# ATMegaBoardReduced.net
KiCad netlist of a schematic drawn in EAGLE
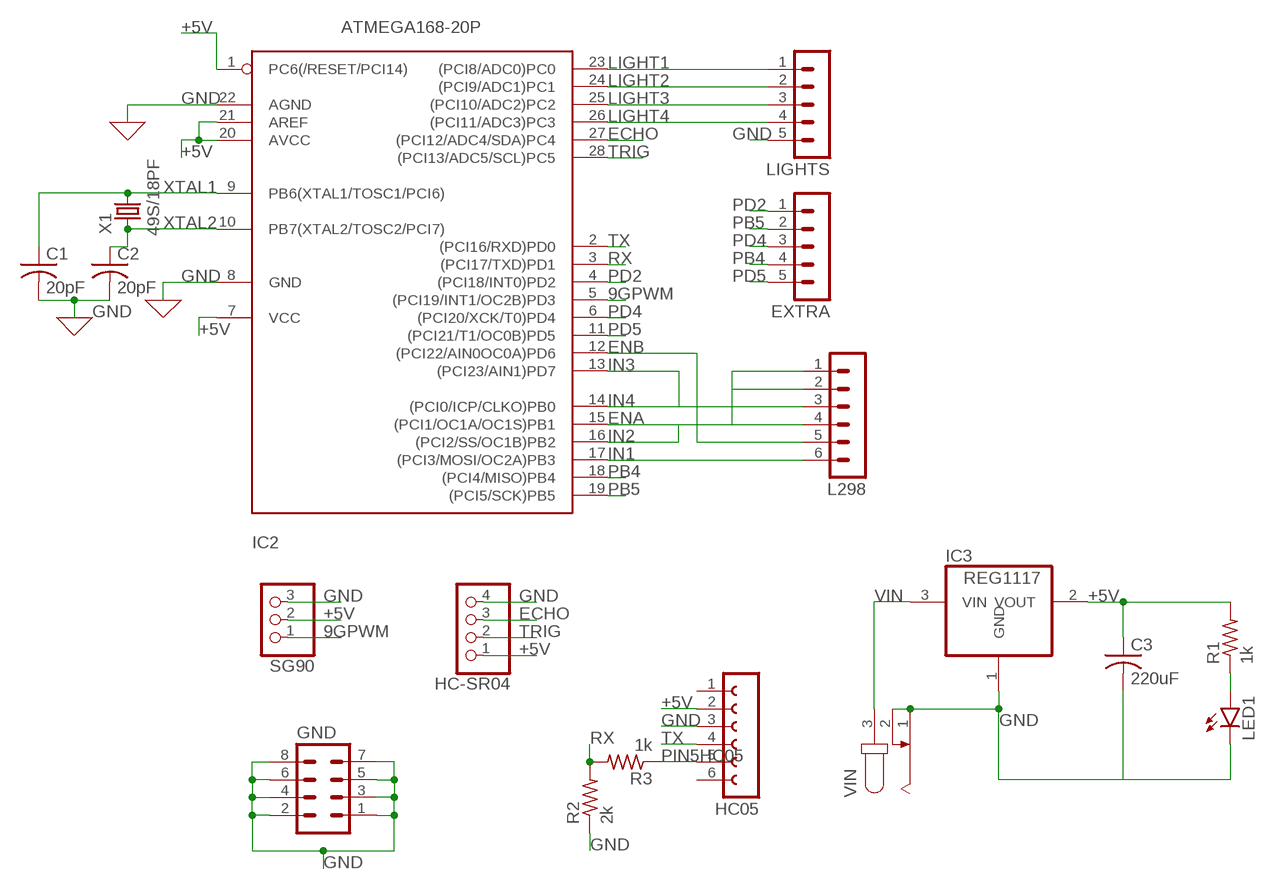
[diagram p0: schematic, sheet 1]

(export (version "E")
  (design (tool "Eeschema 10.0.6"))
  (components
    (comp (ref "C1")
      (value "20pF")
      (footprint "eagle-import:C050-024X044")
      (libsource (lib "eagle-import") (part "C-US050-024X044"))
    )
    (comp (ref "C2")
      (value "20pF")
      (footprint "eagle-import:C050-024X044")
      (libsource (lib "eagle-import") (part "C-US050-024X044"))
    )
    (comp (ref "C3")
      (value "220uF")
      (footprint "eagle-import:C050-024X044")
      (libsource (lib "eagle-import") (part "C-US050-024X044"))
    )
    (comp (ref "EXTRA")
      (value "MA05-1")
      (footprint "eagle-import:MA05-1")
      (libsource (lib "eagle-import") (part "MA05-1"))
    )
    (comp (ref "GND")
      (value "MA04-2")
      (footprint "eagle-import:MA04-2")
      (libsource (lib "eagle-import") (part "MA04-2"))
    )
    (comp (ref "HC-SR04")
      (value "PINHD-1X4")
      (footprint "eagle-import:1X04")
      (libsource (lib "eagle-import") (part "PINHD-1X4"))
    )
    (comp (ref "HC05")
      (value "FE06W")
      (footprint "eagle-import:FE06W")
      (libsource (lib "eagle-import") (part "FE06W"))
    )
    (comp (ref "IC2")
      (value "ATMEGA168-20P")
      (footprint "eagle-import:DIL28-3")
      (libsource (lib "eagle-import") (part "ATMEGA168P-20"))
    )
    (comp (ref "IC3")
      (value "REG1117")
      (footprint "eagle-import:SOT223")
      (libsource (lib "eagle-import") (part "REG1117"))
    )
    (comp (ref "L298")
      (value "MA06-1")
      (footprint "eagle-import:MA06-1")
      (libsource (lib "eagle-import") (part "MA06-1"))
    )
    (comp (ref "LED1")
      (value "LED5MM")
      (footprint "eagle-import:LED5MM")
      (libsource (lib "eagle-import") (part "LED5MM"))
    )
    (comp (ref "LIGHTS")
      (value "MA05-1")
      (footprint "eagle-import:MA05-1")
      (libsource (lib "eagle-import") (part "MA05-1"))
    )
    (comp (ref "R1")
      (value "1k")
      (footprint "eagle-import:0207_10")
      (libsource (lib "eagle-import") (part "R-US_0207/10"))
    )
    (comp (ref "R2")
      (value "2k")
      (footprint "eagle-import:0207_10")
      (libsource (lib "eagle-import") (part "R-US_0207/10"))
    )
    (comp (ref "R3")
      (value "1k")
      (footprint "eagle-import:0207_10")
      (libsource (lib "eagle-import") (part "R-US_0207/10"))
    )
    (comp (ref "SG90")
      (value "PINHD-1X3")
      (footprint "eagle-import:1X03")
      (libsource (lib "eagle-import") (part "PINHD-1X3"))
    )
    (comp (ref "VIN")
      (value "JACK-PLUG1")
      (footprint "eagle-import:SPC4078")
      (libsource (lib "eagle-import") (part "JACK-PLUG1"))
    )
    (comp (ref "X1")
      (value "49S/18PF")
      (footprint "eagle-import:XTAL_HC49")
      (fields (field (name "MANUFACTURER") "Xinhunjing ") (field (name "CREATED_BY") "PCBLayout.com"))
      (libsource (lib "eagle-import") (part "49S/18PF"))
    )
  )
  (nets
    (net (code "1") (name "/+5V") (class "Default")
      (node (ref "C3") (pin "1") (pinfunction "1_1") (pintype "passive"))
      (node (ref "HC-SR04") (pin "1") (pinfunction "1_1") (pintype "passive"))
      (node (ref "HC05") (pin "2") (pinfunction "2_2") (pintype "passive"))
      (node (ref "IC2") (pin "1") (pinfunction "PC6(/RESET/PCI14)_1") (pintype "bidirectional"))
      (node (ref "IC2") (pin "20") (pinfunction "AVCC_20") (pintype "bidirectional"))
      (node (ref "IC2") (pin "21") (pinfunction "AREF_21") (pintype "bidirectional"))
      (node (ref "IC2") (pin "7") (pinfunction "VCC_7") (pintype "bidirectional"))
      (node (ref "IC3") (pin "2") (pinfunction "VOUT_2") (pintype "output"))
      (node (ref "R1") (pin "2") (pinfunction "2_2") (pintype "passive"))
      (node (ref "SG90") (pin "2") (pinfunction "2_2") (pintype "passive"))
    )
    (net (code "2") (name "/9GPWM") (class "Default")
      (node (ref "IC2") (pin "5") (pinfunction "(PCI19/INT1/OC2B)PD3_5") (pintype "bidirectional"))
      (node (ref "SG90") (pin "1") (pinfunction "1_1") (pintype "passive"))
    )
    (net (code "3") (name "/ECHO") (class "Default")
      (node (ref "HC-SR04") (pin "3") (pinfunction "3_3") (pintype "passive"))
      (node (ref "IC2") (pin "27") (pinfunction "(PCI12/ADC4/SDA)PC4_27") (pintype "bidirectional"))
    )
    (net (code "4") (name "/ENA") (class "Default")
      (node (ref "IC2") (pin "15") (pinfunction "(PCI1/OC1A/OC1S)PB1_15") (pintype "bidirectional"))
      (node (ref "L298") (pin "2") (pinfunction "2_2") (pintype "passive"))
    )
    (net (code "5") (name "/ENB") (class "Default")
      (node (ref "IC2") (pin "12") (pinfunction "(PCI22/AIN0OC0A)PD6_12") (pintype "bidirectional"))
      (node (ref "L298") (pin "5") (pinfunction "5_5") (pintype "passive"))
    )
    (net (code "6") (name "/IN1") (class "Default")
      (node (ref "IC2") (pin "17") (pinfunction "(PCI3/MOSI/OC2A)PB3_17") (pintype "bidirectional"))
      (node (ref "L298") (pin "6") (pinfunction "6_6") (pintype "passive"))
    )
    (net (code "7") (name "/IN2") (class "Default")
      (node (ref "IC2") (pin "16") (pinfunction "(PCI2/SS/OC1B)PB2_16") (pintype "bidirectional"))
      (node (ref "L298") (pin "4") (pinfunction "4_4") (pintype "passive"))
    )
    (net (code "8") (name "/IN3") (class "Default")
      (node (ref "IC2") (pin "13") (pinfunction "(PCI23/AIN1)PD7_13") (pintype "bidirectional"))
      (node (ref "L298") (pin "3") (pinfunction "3_3") (pintype "passive"))
    )
    (net (code "9") (name "/IN4") (class "Default")
      (node (ref "IC2") (pin "14") (pinfunction "(PCI0/ICP/CLKO)PB0_14") (pintype "bidirectional"))
      (node (ref "L298") (pin "1") (pinfunction "1_1") (pintype "passive"))
    )
    (net (code "10") (name "/LIGHT1") (class "Default")
      (node (ref "IC2") (pin "23") (pinfunction "(PCI8/ADC0)PC0_23") (pintype "bidirectional"))
      (node (ref "LIGHTS") (pin "1") (pinfunction "1_1") (pintype "passive"))
    )
    (net (code "11") (name "/LIGHT2") (class "Default")
      (node (ref "IC2") (pin "24") (pinfunction "(PCI9/ADC1)PC1_24") (pintype "bidirectional"))
      (node (ref "LIGHTS") (pin "2") (pinfunction "2_2") (pintype "passive"))
    )
    (net (code "12") (name "/LIGHT3") (class "Default")
      (node (ref "IC2") (pin "25") (pinfunction "(PCI10/ADC2)PC2_25") (pintype "bidirectional"))
      (node (ref "LIGHTS") (pin "3") (pinfunction "3_3") (pintype "passive"))
    )
    (net (code "13") (name "/LIGHT4") (class "Default")
      (node (ref "IC2") (pin "26") (pinfunction "(PCI11/ADC3)PC3_26") (pintype "bidirectional"))
      (node (ref "LIGHTS") (pin "4") (pinfunction "4_4") (pintype "passive"))
    )
    (net (code "14") (name "/PB4") (class "Default")
      (node (ref "EXTRA") (pin "4") (pinfunction "4_4") (pintype "passive"))
      (node (ref "IC2") (pin "18") (pinfunction "(PCI4/MISO)PB4_18") (pintype "bidirectional"))
    )
    (net (code "15") (name "/PB5") (class "Default")
      (node (ref "EXTRA") (pin "2") (pinfunction "2_2") (pintype "passive"))
      (node (ref "IC2") (pin "19") (pinfunction "(PCI5/SCK)PB5_19") (pintype "bidirectional"))
    )
    (net (code "16") (name "/PD2") (class "Default")
      (node (ref "EXTRA") (pin "1") (pinfunction "1_1") (pintype "passive"))
      (node (ref "IC2") (pin "4") (pinfunction "(PCI18/INT0)PD2_4") (pintype "bidirectional"))
    )
    (net (code "17") (name "/PD4") (class "Default")
      (node (ref "EXTRA") (pin "3") (pinfunction "3_3") (pintype "passive"))
      (node (ref "IC2") (pin "6") (pinfunction "(PCI20/XCK/T0)PD4_6") (pintype "bidirectional"))
    )
    (net (code "18") (name "/PD5") (class "Default")
      (node (ref "EXTRA") (pin "5") (pinfunction "5_5") (pintype "passive"))
      (node (ref "IC2") (pin "11") (pinfunction "(PCI21/T1/OC0B)PD5_11") (pintype "bidirectional"))
    )
    (net (code "19") (name "/PIN5HC05") (class "Default")
      (node (ref "HC05") (pin "5") (pinfunction "5_5") (pintype "passive"))
      (node (ref "R3") (pin "1") (pinfunction "1_1") (pintype "passive"))
    )
    (net (code "20") (name "/RX") (class "Default")
      (node (ref "IC2") (pin "3") (pinfunction "(PCI17/TXD)PD1_3") (pintype "bidirectional"))
      (node (ref "R2") (pin "2") (pinfunction "2_2") (pintype "passive"))
      (node (ref "R3") (pin "2") (pinfunction "2_2") (pintype "passive"))
    )
    (net (code "21") (name "/TRIG") (class "Default")
      (node (ref "HC-SR04") (pin "2") (pinfunction "2_2") (pintype "passive"))
      (node (ref "IC2") (pin "28") (pinfunction "(PCI13/ADC5/SCL)PC5_28") (pintype "bidirectional"))
    )
    (net (code "22") (name "/TX") (class "Default")
      (node (ref "HC05") (pin "4") (pinfunction "4_4") (pintype "passive"))
      (node (ref "IC2") (pin "2") (pinfunction "(PCI16/RXD)PD0_2") (pintype "bidirectional"))
    )
    (net (code "23") (name "/VIN") (class "Default")
      (node (ref "IC3") (pin "3") (pinfunction "VIN_3") (pintype "input"))
      (node (ref "VIN") (pin "3") (pinfunction "3_3") (pintype "passive"))
    )
    (net (code "24") (name "/XTAL1") (class "Default")
      (node (ref "C1") (pin "1") (pinfunction "1_1") (pintype "passive"))
      (node (ref "IC2") (pin "9") (pinfunction "PB6(XTAL1/TOSC1/PCI6)_9") (pintype "bidirectional"))
      (node (ref "X1") (pin "2") (pinfunction "2_2") (pintype "passive"))
    )
    (net (code "25") (name "/XTAL2") (class "Default")
      (node (ref "C2") (pin "1") (pinfunction "1_1") (pintype "passive"))
      (node (ref "IC2") (pin "10") (pinfunction "PB7(XTAL2/TOSC2/PCI7)_10") (pintype "bidirectional"))
      (node (ref "X1") (pin "1") (pinfunction "1_1") (pintype "passive"))
    )
    (net (code "26") (name "GND") (class "Default")
      (node (ref "C1") (pin "2") (pinfunction "2_2") (pintype "passive"))
      (node (ref "C2") (pin "2") (pinfunction "2_2") (pintype "passive"))
      (node (ref "C3") (pin "2") (pinfunction "2_2") (pintype "passive"))
      (node (ref "GND") (pin "1") (pinfunction "1_1") (pintype "passive"))
      (node (ref "GND") (pin "2") (pinfunction "2_2") (pintype "passive"))
      (node (ref "GND") (pin "3") (pinfunction "3_3") (pintype "passive"))
      (node (ref "GND") (pin "4") (pinfunction "4_4") (pintype "passive"))
      (node (ref "GND") (pin "5") (pinfunction "5_5") (pintype "passive"))
      (node (ref "GND") (pin "6") (pinfunction "6_6") (pintype "passive"))
      (node (ref "GND") (pin "7") (pinfunction "7_7") (pintype "passive"))
      (node (ref "GND") (pin "8") (pinfunction "8_8") (pintype "passive"))
      (node (ref "HC-SR04") (pin "4") (pinfunction "4_4") (pintype "passive"))
      (node (ref "HC05") (pin "3") (pinfunction "3_3") (pintype "passive"))
      (node (ref "IC2") (pin "22") (pinfunction "AGND_22") (pintype "bidirectional"))
      (node (ref "IC2") (pin "8") (pinfunction "GND_8") (pintype "bidirectional"))
      (node (ref "IC3") (pin "1") (pinfunction "GND_1") (pintype "power_in"))
      (node (ref "LED1") (pin "K") (pinfunction "C_K") (pintype "passive"))
      (node (ref "LIGHTS") (pin "5") (pinfunction "5_5") (pintype "passive"))
      (node (ref "R2") (pin "1") (pinfunction "1_1") (pintype "passive"))
      (node (ref "SG90") (pin "3") (pinfunction "3_3") (pintype "passive"))
      (node (ref "VIN") (pin "1") (pinfunction "1_1") (pintype "passive"))
      (node (ref "VIN") (pin "2") (pinfunction "2_2") (pintype "passive"))
    )
    (net (code "27") (name "Net-(LED1-PadA)") (class "Default")
      (node (ref "LED1") (pin "A") (pinfunction "A_A") (pintype "passive"))
      (node (ref "R1") (pin "1") (pinfunction "1_1") (pintype "passive"))
    )
    (net (code "28") (name "unconnected-(HC05-Pad1)") (class "Default")
      (node (ref "HC05") (pin "1") (pinfunction "1_1") (pintype "passive"))
    )
    (net (code "29") (name "unconnected-(HC05-Pad6)") (class "Default")
      (node (ref "HC05") (pin "6") (pinfunction "6_6") (pintype "passive"))
    )
  )
)
